# Bluetooth.net
KiCad netlist of a schematic drawn in Altium Designer
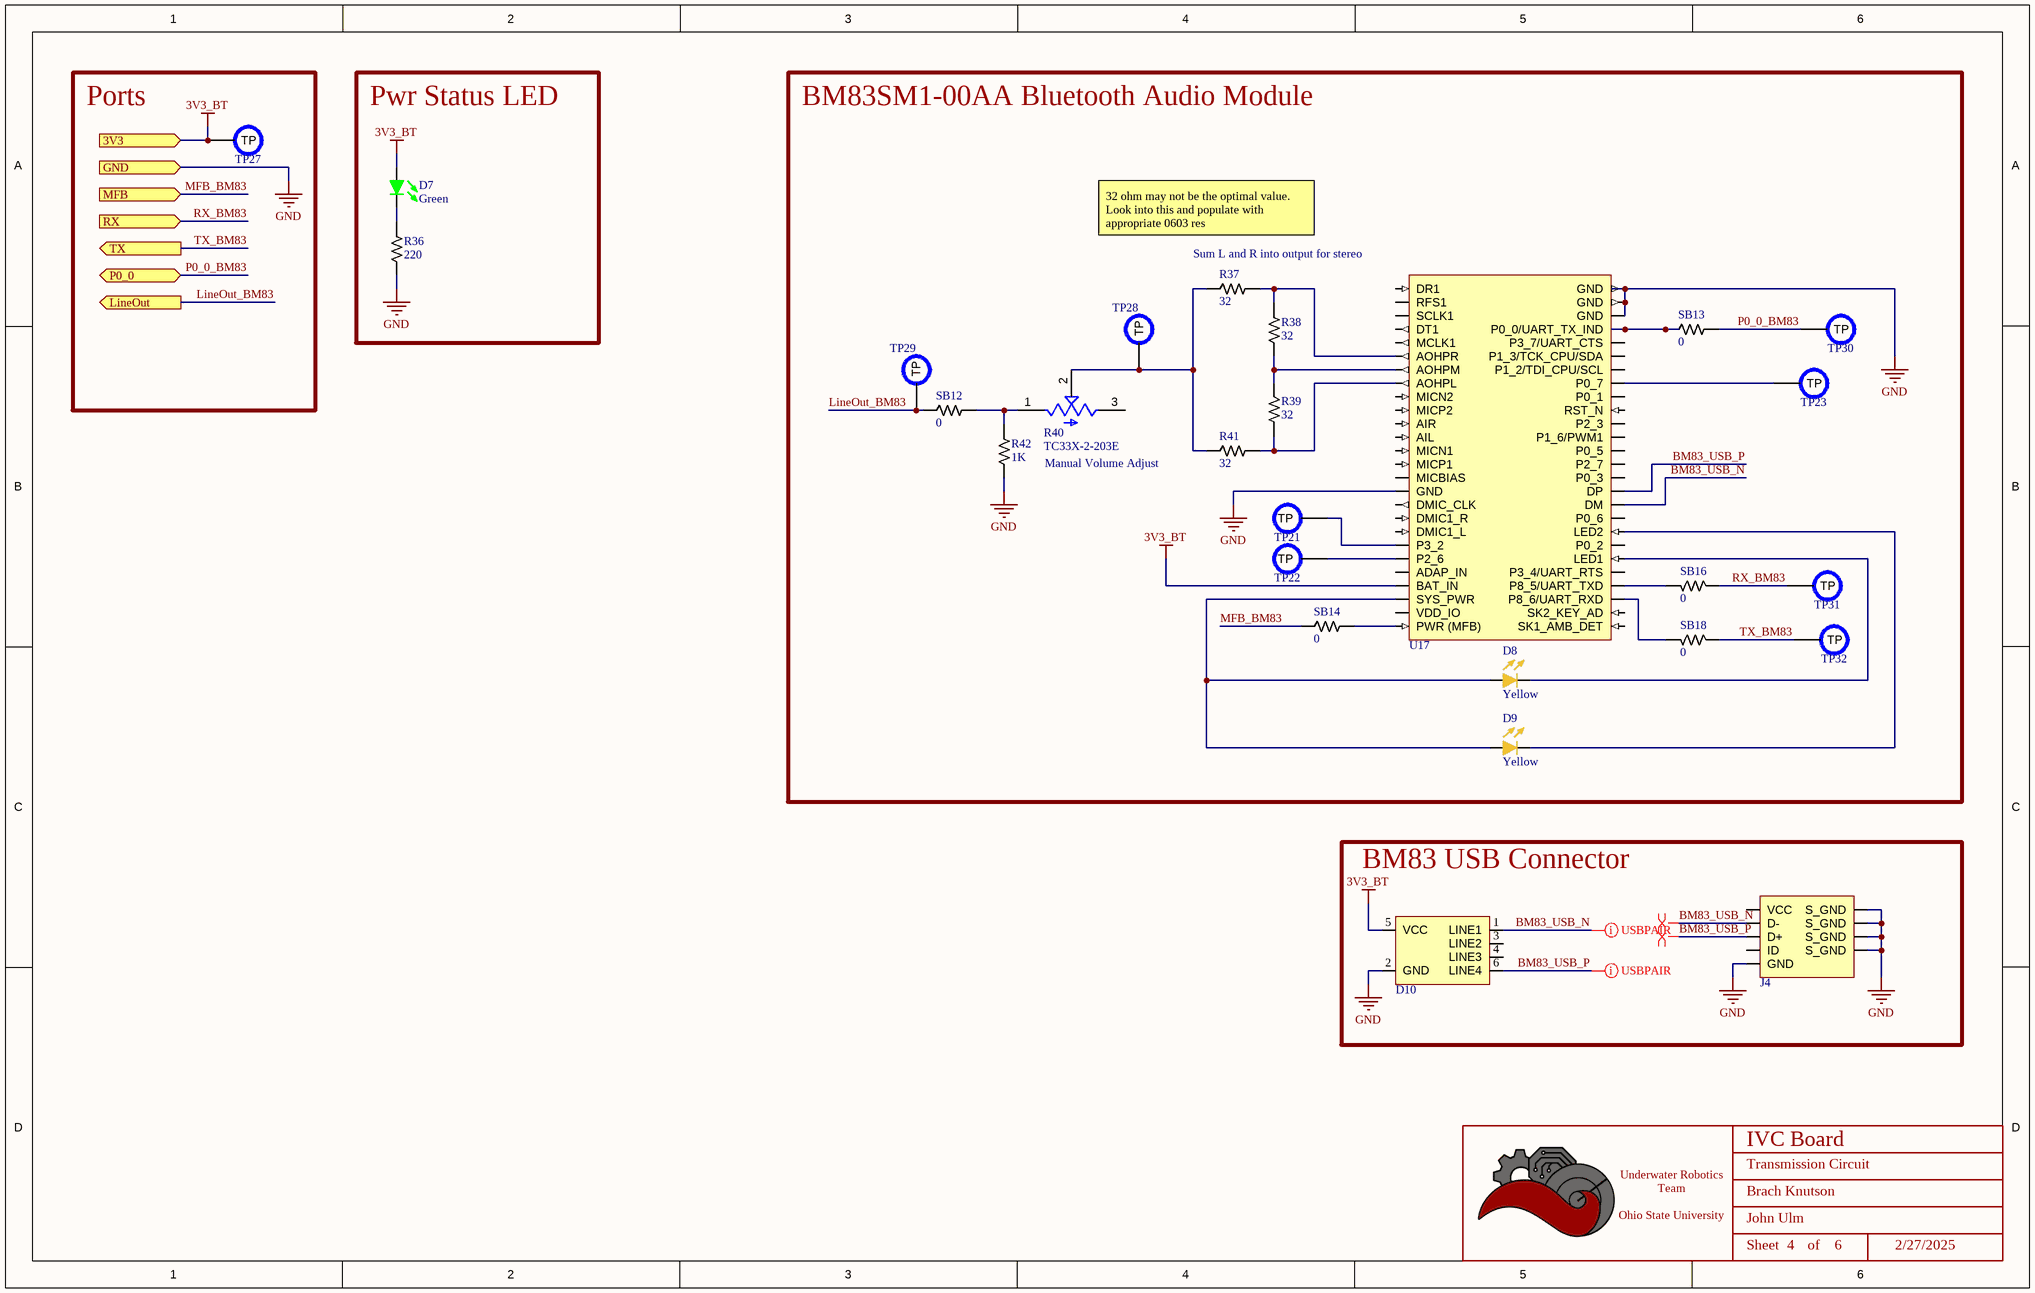
[diagram p0: Bluetooth.SchDoc]

(export (version "E")
  (design (tool "Eeschema 10.0.6"))
  (components
    (comp (ref "D7")
      (value "150060GS75000")
      (footprint "LED_0603")
      (description "LED Green Vf= 3.2V If = 0.025A\r\n150060GS75000")
      (fields (field (name "COLOR") "Green") (field (name "MADE BY") "Flip B"))
      (libsource (lib "Diodes") (part "LED_Green_0603_3.2V"))
    )
    (comp (ref "D8")
      (value "150060YS75000")
      (footprint "LED_0603")
      (description "LED Yellow Vf= 2V If = 0.020A\r\n150060YS75000")
      (fields (field (name "COLOR") "Yellow") (field (name "MADE BY") "Robert Pafford"))
      (libsource (lib "Diodes") (part "LED_Yellow_0603"))
    )
    (comp (ref "D9")
      (value "150060YS75000")
      (footprint "LED_0603")
      (description "LED Yellow Vf= 2V If = 0.020A\r\n150060YS75000")
      (fields (field (name "COLOR") "Yellow") (field (name "MADE BY") "Robert Pafford"))
      (libsource (lib "Diodes") (part "LED_Yellow_0603"))
    )
    (comp (ref "D10")
      (value "TVS DIODE 5VWM 25VC SOT23-6")
      (footprint "SOT 23-6L")
      (description "25V Clamp 6A (8/20µs) Ipp Tvs Diode Surface Mount SOT-23-6")
      (fields (field (name "MADE BY") "Robert Pafford"))
      (libsource (lib "Diodes") (part "RCLAMP0504S.TCT"))
    )
    (comp (ref "J4")
      (value "USB_MICRO R/A")
      (footprint "CONN_MINIUSB")
      (description "Amphenol Micro USB-B\r\nUSB2.0 5 Pin Right Angle SMD")
      (fields (field (name "MANUFACTURER") "Amphenol") (field (name "CREATED BY") "Flip B"))
      (libsource (lib "Connectors") (part "CONN_MICROUSB"))
    )
    (comp (ref "R36")
      (value "220 Ohm 5% 1/8W")
      (footprint "RESISTOR_0603")
      (description "RES 220 OHM 5% 1/8W 0603")
      (fields
        (field (name "TOLERANCE") "+/- 5%")
        (field (name "VALUE  (OHMS)") "220")
        (field (name "MADE BY") "John S")
      )
      (libsource (lib "Resistors") (part "RESISTOR_200_0603"))
    )
    (comp (ref "R37")
      (value "32")
      (footprint "RESISTOR_0603")
      (fields (field (name "Comment") "RN73R1JTTD32R0D25"))
      (libsource (lib "Resistors") (part "RES 32 OHM 0.5% 1/10W 0603"))
    )
    (comp (ref "R38")
      (value "32")
      (footprint "RESISTOR_0603")
      (fields (field (name "Comment") "RN73R1JTTD32R0D25"))
      (libsource (lib "Resistors") (part "RES 32 OHM 0.5% 1/10W 0603"))
    )
    (comp (ref "R39")
      (value "32")
      (footprint "RESISTOR_0603")
      (fields (field (name "Comment") "RN73R1JTTD32R0D25"))
      (libsource (lib "Resistors") (part "RES 32 OHM 0.5% 1/10W 0603"))
    )
    (comp (ref "R40")
      (value "TC33X-2-203E")
      (footprint "TRIM_TC33X-2-203E")
      (description "20 kOhms 0.1W, 1/10W J Lead Surface Mount Trimmer Potentiometer Cermet 1 Turn Top Adjustment")
      (fields (field (name "MF") "Bourns") (field (name "DIGI-KEY_PART_NUMBER") "TC33X-2-203ECT-ND"))
      (libsource (lib "Resistors") (part "TC33X-2-203E"))
    )
    (comp (ref "R41")
      (value "32")
      (footprint "RESISTOR_0603")
      (fields (field (name "Comment") "RN73R1JTTD32R0D25"))
      (libsource (lib "Resistors") (part "RES 32 OHM 0.5% 1/10W 0603"))
    )
    (comp (ref "R42")
      (value "1k Ohm 5% 1/8W")
      (footprint "RESISTOR_0603")
      (description "RES 1k OHM 5% 1/8W 0603")
      (fields
        (field (name "TOLERANCE") "+/- 5%")
        (field (name "VALUE  (OHMS)") "1K")
        (field (name "MADE BY") "Robert Pafford")
      )
      (libsource (lib "Resistors") (part "RESISTOR_1K_0603"))
    )
    (comp (ref "SB12")
      (value "0 Ohm Jumper No Fit")
      (footprint "RESISTOR_0603")
      (description "0 Ohm Jumper No Fit for Solder Bridge")
      (fields (field (name "VALUE  (OHMS)") "0") (field (name "MADE BY") "Robert Pafford"))
      (libsource (lib "Resistors") (part "JUMPER_0_0603"))
    )
    (comp (ref "SB13")
      (value "0 Ohm Jumper No Fit")
      (footprint "RESISTOR_0603")
      (description "0 Ohm Jumper No Fit for Solder Bridge")
      (fields (field (name "VALUE  (OHMS)") "0") (field (name "MADE BY") "Robert Pafford"))
      (libsource (lib "Resistors") (part "JUMPER_0_0603"))
    )
    (comp (ref "SB14")
      (value "0 Ohm Jumper No Fit")
      (footprint "RESISTOR_0603")
      (description "0 Ohm Jumper No Fit for Solder Bridge")
      (fields (field (name "VALUE  (OHMS)") "0") (field (name "MADE BY") "Robert Pafford"))
      (libsource (lib "Resistors") (part "JUMPER_0_0603"))
    )
    (comp (ref "SB16")
      (value "0 Ohm Jumper No Fit")
      (footprint "RESISTOR_0603")
      (description "0 Ohm Jumper No Fit for Solder Bridge")
      (fields (field (name "VALUE  (OHMS)") "0") (field (name "MADE BY") "Robert Pafford"))
      (libsource (lib "Resistors") (part "JUMPER_0_0603"))
    )
    (comp (ref "SB18")
      (value "0 Ohm Jumper No Fit")
      (footprint "RESISTOR_0603")
      (description "0 Ohm Jumper No Fit for Solder Bridge")
      (fields (field (name "VALUE  (OHMS)") "0") (field (name "MADE BY") "Robert Pafford"))
      (libsource (lib "Resistors") (part "JUMPER_0_0603"))
    )
    (comp (ref "TP21")
      (value "PCB Test Point")
      (footprint "TESTPOINT_1.2MM")
      (fields (field (name "MADE BY") "Robert Pafford"))
      (libsource (lib "Connectors") (part "TESTPOINT"))
    )
    (comp (ref "TP22")
      (value "PCB Test Point")
      (footprint "TESTPOINT_1.2MM")
      (fields (field (name "MADE BY") "Robert Pafford"))
      (libsource (lib "Connectors") (part "TESTPOINT"))
    )
    (comp (ref "TP23")
      (value "PCB Test Point")
      (footprint "TESTPOINT_1.2MM")
      (fields (field (name "MADE BY") "Robert Pafford"))
      (libsource (lib "Connectors") (part "TESTPOINT"))
    )
    (comp (ref "TP27")
      (value "PCB Test Point")
      (footprint "TESTPOINT_1.2MM")
      (fields (field (name "MADE BY") "Robert Pafford"))
      (libsource (lib "Connectors") (part "TESTPOINT"))
    )
    (comp (ref "TP28")
      (value "PCB Test Point")
      (footprint "TESTPOINT_1.2MM")
      (fields (field (name "MADE BY") "Robert Pafford"))
      (libsource (lib "Connectors") (part "TESTPOINT"))
    )
    (comp (ref "TP29")
      (value "PCB Test Point")
      (footprint "TESTPOINT_1.2MM")
      (fields (field (name "MADE BY") "Robert Pafford"))
      (libsource (lib "Connectors") (part "TESTPOINT"))
    )
    (comp (ref "TP30")
      (value "PCB Test Point")
      (footprint "TESTPOINT_1.2MM")
      (fields (field (name "MADE BY") "Robert Pafford"))
      (libsource (lib "Connectors") (part "TESTPOINT"))
    )
    (comp (ref "TP31")
      (value "PCB Test Point")
      (footprint "TESTPOINT_1.2MM")
      (fields (field (name "MADE BY") "Robert Pafford"))
      (libsource (lib "Connectors") (part "TESTPOINT"))
    )
    (comp (ref "TP32")
      (value "PCB Test Point")
      (footprint "TESTPOINT_1.2MM")
      (fields (field (name "MADE BY") "Robert Pafford"))
      (libsource (lib "Connectors") (part "TESTPOINT"))
    )
    (comp (ref "U17")
      (value "RF TXRX MOD BT PCB TH SMD")
      (footprint "BM83SM1-00AA")
      (description "Bluetooth Bluetooth v5.0 Transceiver Module 2.4GHz ~ 2.48GHz PCB Trace Surface Mount")
      (libsource (lib "Modules") (part "BM83SM1-00AA"))
    )
  )
  (nets
    (net (code "1") (name "/BM83_USB_N") (class "Default")
      (node (ref "D10") (pin "1") (pinfunction "LINE1_1") (pintype "passive"))
      (node (ref "J4") (pin "2") (pinfunction "D-_2") (pintype "passive"))
      (node (ref "U17") (pin "36") (pinfunction "DM_36") (pintype "bidirectional"))
    )
    (net (code "2") (name "/BM83_USB_P") (class "Default")
      (node (ref "D10") (pin "6") (pinfunction "LINE4_6") (pintype "passive"))
      (node (ref "J4") (pin "3") (pinfunction "D+_3") (pintype "passive"))
      (node (ref "U17") (pin "37") (pinfunction "DP_37") (pintype "bidirectional"))
    )
    (net (code "3") (name "/LineOut_BM83") (class "Default")
      (node (ref "SB12") (pin "2") (pinfunction "2_2") (pintype "passive"))
      (node (ref "TP29") (pin "TP") (pinfunction "TP_TP") (pintype "passive"))
    )
    (net (code "4") (name "/MFB_BM83") (class "Default")
      (node (ref "SB14") (pin "2") (pinfunction "2_2") (pintype "passive"))
    )
    (net (code "5") (name "/P0_0_BM83") (class "Default")
      (node (ref "SB13") (pin "1") (pinfunction "1_1") (pintype "passive"))
      (node (ref "TP30") (pin "TP") (pinfunction "TP_TP") (pintype "passive"))
    )
    (net (code "6") (name "/RX_BM83") (class "Default")
      (node (ref "SB16") (pin "2") (pinfunction "2_2") (pintype "passive"))
      (node (ref "TP31") (pin "TP") (pinfunction "TP_TP") (pintype "passive"))
    )
    (net (code "7") (name "/TX_BM83") (class "Default")
      (node (ref "SB18") (pin "2") (pinfunction "2_2") (pintype "passive"))
      (node (ref "TP32") (pin "TP") (pinfunction "TP_TP") (pintype "passive"))
    )
    (net (code "8") (name "3V3_BT") (class "Default")
      (node (ref "D10") (pin "5") (pinfunction "VCC_5") (pintype "power_in"))
      (node (ref "D7") (pin "1") (pinfunction "1_1") (pintype "passive"))
      (node (ref "TP27") (pin "TP") (pinfunction "TP_TP") (pintype "passive"))
      (node (ref "U17") (pin "23") (pinfunction "BAT_IN_23") (pintype "power_in"))
    )
    (net (code "9") (name "GND") (class "Default")
      (node (ref "D10") (pin "2") (pinfunction "GND_2") (pintype "power_in"))
      (node (ref "J4") (pin "5") (pinfunction "GND_5") (pintype "passive"))
      (node (ref "J4") (pin "6") (pinfunction "S_GND_6") (pintype "passive"))
      (node (ref "J4") (pin "7") (pinfunction "S_GND_7") (pintype "passive"))
      (node (ref "J4") (pin "8") (pinfunction "S_GND_8") (pintype "passive"))
      (node (ref "J4") (pin "9") (pinfunction "S_GND_9") (pintype "passive"))
      (node (ref "R36") (pin "2") (pinfunction "2_2") (pintype "passive"))
      (node (ref "R42") (pin "2") (pinfunction "2_2") (pintype "passive"))
      (node (ref "U17") (pin "16") (pinfunction "GND_16") (pintype "power_in"))
      (node (ref "U17") (pin "50") (pinfunction "GND_50") (pintype "power_in"))
      (node (ref "U17") (pin "51") (pinfunction "GND_51") (pintype "output"))
      (node (ref "U17") (pin "52") (pinfunction "GND_52") (pintype "output"))
    )
    (net (code "10") (name "Net-(D7-Pad2)") (class "Default")
      (node (ref "D7") (pin "2") (pinfunction "2_2") (pintype "passive"))
      (node (ref "R36") (pin "1") (pinfunction "1_1") (pintype "passive"))
    )
    (net (code "11") (name "Net-(R40-CCW)") (class "Default")
      (node (ref "R40") (pin "1") (pinfunction "CCW_1") (pintype "passive"))
      (node (ref "R42") (pin "1") (pinfunction "1_1") (pintype "passive"))
      (node (ref "SB12") (pin "1") (pinfunction "1_1") (pintype "passive"))
    )
    (net (code "12") (name "Net-(R40-W)") (class "Default")
      (node (ref "R37") (pin "2") (pinfunction "2_2") (pintype "passive"))
      (node (ref "R40") (pin "2") (pinfunction "W_2") (pintype "passive"))
      (node (ref "R41") (pin "2") (pinfunction "2_2") (pintype "passive"))
      (node (ref "TP28") (pin "TP") (pinfunction "TP_TP") (pintype "passive"))
    )
    (net (code "13") (name "Net-(U17-AOHPL)") (class "Default")
      (node (ref "R39") (pin "1") (pinfunction "1_1") (pintype "passive"))
      (node (ref "R41") (pin "1") (pinfunction "1_1") (pintype "passive"))
      (node (ref "U17") (pin "8") (pinfunction "AOHPL_8") (pintype "output"))
    )
    (net (code "14") (name "Net-(U17-AOHPM)") (class "Default")
      (node (ref "R38") (pin "2") (pinfunction "2_2") (pintype "passive"))
      (node (ref "R39") (pin "2") (pinfunction "2_2") (pintype "passive"))
      (node (ref "U17") (pin "7") (pinfunction "AOHPM_7") (pintype "output"))
    )
    (net (code "15") (name "Net-(U17-AOHPR)") (class "Default")
      (node (ref "R37") (pin "1") (pinfunction "1_1") (pintype "passive"))
      (node (ref "R38") (pin "1") (pinfunction "1_1") (pintype "passive"))
      (node (ref "U17") (pin "6") (pinfunction "AOHPR_6") (pintype "output"))
    )
    (net (code "16") (name "Net-(U17-LED1)") (class "Default")
      (node (ref "D8") (pin "2") (pinfunction "2_2") (pintype "passive"))
      (node (ref "U17") (pin "32") (pinfunction "LED1_32") (pintype "input"))
    )
    (net (code "17") (name "Net-(U17-LED2)") (class "Default")
      (node (ref "D9") (pin "2") (pinfunction "2_2") (pintype "passive"))
      (node (ref "U17") (pin "34") (pinfunction "LED2_34") (pintype "input"))
    )
    (net (code "18") (name "Net-(U17-P0_0{slash}UART_TX_IND)") (class "Default")
      (node (ref "SB13") (pin "2") (pinfunction "2_2") (pintype "passive"))
      (node (ref "U17") (pin "49") (pinfunction "P0_0/UART_TX_IND_49") (pintype "bidirectional"))
    )
    (net (code "19") (name "Net-(U17-P0_7)") (class "Default")
      (node (ref "TP23") (pin "TP") (pinfunction "TP_TP") (pintype "passive"))
      (node (ref "U17") (pin "45") (pinfunction "P0_7_45") (pintype "bidirectional"))
    )
    (net (code "20") (name "Net-(U17-P2_6)") (class "Default")
      (node (ref "TP22") (pin "TP") (pinfunction "TP_TP") (pintype "passive"))
      (node (ref "U17") (pin "21") (pinfunction "P2_6_21") (pintype "bidirectional"))
    )
    (net (code "21") (name "Net-(U17-P3_2)") (class "Default")
      (node (ref "TP21") (pin "TP") (pinfunction "TP_TP") (pintype "passive"))
      (node (ref "U17") (pin "20") (pinfunction "P3_2_20") (pintype "bidirectional"))
    )
    (net (code "22") (name "Net-(U17-P8_5{slash}UART_TXD)") (class "Default")
      (node (ref "SB16") (pin "1") (pinfunction "1_1") (pintype "passive"))
      (node (ref "U17") (pin "30") (pinfunction "P8_5/UART_TXD_30") (pintype "bidirectional"))
    )
    (net (code "23") (name "Net-(U17-P8_6{slash}UART_RXD)") (class "Default")
      (node (ref "SB18") (pin "1") (pinfunction "1_1") (pintype "passive"))
      (node (ref "U17") (pin "29") (pinfunction "P8_6/UART_RXD_29") (pintype "bidirectional"))
    )
    (net (code "24") (name "Net-(U17-PWR_(MFB))") (class "Default")
      (node (ref "SB14") (pin "1") (pinfunction "1_1") (pintype "passive"))
      (node (ref "U17") (pin "26") (pinfunction "PWR_(MFB)_26") (pintype "input"))
    )
    (net (code "25") (name "Net-(U17-SYS_PWR)") (class "Default")
      (node (ref "D8") (pin "1") (pinfunction "1_1") (pintype "passive"))
      (node (ref "D9") (pin "1") (pinfunction "1_1") (pintype "passive"))
      (node (ref "U17") (pin "24") (pinfunction "SYS_PWR_24") (pintype "power_in"))
    )
    (net (code "26") (name "unconnected-(D10-LINE2-Pad3)") (class "Default")
      (node (ref "D10") (pin "3") (pinfunction "LINE2_3") (pintype "passive"))
    )
    (net (code "27") (name "unconnected-(D10-LINE3-Pad4)") (class "Default")
      (node (ref "D10") (pin "4") (pinfunction "LINE3_4") (pintype "passive"))
    )
    (net (code "28") (name "unconnected-(J4-ID-Pad4)") (class "Default")
      (node (ref "J4") (pin "4") (pinfunction "ID_4") (pintype "passive"))
    )
    (net (code "29") (name "unconnected-(J4-VCC-Pad1)") (class "Default")
      (node (ref "J4") (pin "1") (pinfunction "VCC_1") (pintype "passive"))
    )
    (net (code "30") (name "unconnected-(R40-CW-Pad3)") (class "Default")
      (node (ref "R40") (pin "3") (pinfunction "CW_3") (pintype "passive"))
    )
    (net (code "31") (name "unconnected-(U17-ADAP_IN-Pad22)") (class "Default")
      (node (ref "U17") (pin "22") (pinfunction "ADAP_IN_22") (pintype "power_in"))
    )
    (net (code "32") (name "unconnected-(U17-AIL-Pad12)") (class "Default")
      (node (ref "U17") (pin "12") (pinfunction "AIL_12") (pintype "input"))
    )
    (net (code "33") (name "unconnected-(U17-AIR-Pad11)") (class "Default")
      (node (ref "U17") (pin "11") (pinfunction "AIR_11") (pintype "input"))
    )
    (net (code "34") (name "unconnected-(U17-DMIC1_L-Pad19)") (class "Default")
      (node (ref "U17") (pin "19") (pinfunction "DMIC1_L_19") (pintype "input"))
    )
    (net (code "35") (name "unconnected-(U17-DMIC1_R-Pad18)") (class "Default")
      (node (ref "U17") (pin "18") (pinfunction "DMIC1_R_18") (pintype "input"))
    )
    (net (code "36") (name "unconnected-(U17-DMIC_CLK-Pad17)") (class "Default")
      (node (ref "U17") (pin "17") (pinfunction "DMIC_CLK_17") (pintype "output"))
    )
    (net (code "37") (name "unconnected-(U17-DR1-Pad1)") (class "Default")
      (node (ref "U17") (pin "1") (pinfunction "DR1_1") (pintype "input"))
    )
    (net (code "38") (name "unconnected-(U17-DT1-Pad4)") (class "Default")
      (node (ref "U17") (pin "4") (pinfunction "DT1_4") (pintype "output"))
    )
    (net (code "39") (name "unconnected-(U17-MCLK1-Pad5)") (class "Default")
      (node (ref "U17") (pin "5") (pinfunction "MCLK1_5") (pintype "output"))
    )
    (net (code "40") (name "unconnected-(U17-MICBIAS-Pad15)") (class "Default")
      (node (ref "U17") (pin "15") (pinfunction "MICBIAS_15") (pintype "power_in"))
    )
    (net (code "41") (name "unconnected-(U17-MICN1-Pad13)") (class "Default")
      (node (ref "U17") (pin "13") (pinfunction "MICN1_13") (pintype "input"))
    )
    (net (code "42") (name "unconnected-(U17-MICN2-Pad9)") (class "Default")
      (node (ref "U17") (pin "9") (pinfunction "MICN2_9") (pintype "input"))
    )
    (net (code "43") (name "unconnected-(U17-MICP1-Pad14)") (class "Default")
      (node (ref "U17") (pin "14") (pinfunction "MICP1_14") (pintype "input"))
    )
    (net (code "44") (name "unconnected-(U17-MICP2-Pad10)") (class "Default")
      (node (ref "U17") (pin "10") (pinfunction "MICP2_10") (pintype "input"))
    )
    (net (code "45") (name "unconnected-(U17-P0_1-Pad44)") (class "Default")
      (node (ref "U17") (pin "44") (pinfunction "P0_1_44") (pintype "bidirectional"))
    )
    (net (code "46") (name "unconnected-(U17-P0_2-Pad33)") (class "Default")
      (node (ref "U17") (pin "33") (pinfunction "P0_2_33") (pintype "bidirectional"))
    )
    (net (code "47") (name "unconnected-(U17-P0_3-Pad38)") (class "Default")
      (node (ref "U17") (pin "38") (pinfunction "P0_3_38") (pintype "bidirectional"))
    )
    (net (code "48") (name "unconnected-(U17-P0_5-Pad40)") (class "Default")
      (node (ref "U17") (pin "40") (pinfunction "P0_5_40") (pintype "bidirectional"))
    )
    (net (code "49") (name "unconnected-(U17-P0_6-Pad35)") (class "Default")
      (node (ref "U17") (pin "35") (pinfunction "P0_6_35") (pintype "bidirectional"))
    )
    (net (code "50") (name "unconnected-(U17-P1_2{slash}TDI_CPU{slash}SCL-Pad46)") (class "Default")
      (node (ref "U17") (pin "46") (pinfunction "P1_2/TDI_CPU/SCL_46") (pintype "bidirectional"))
    )
    (net (code "51") (name "unconnected-(U17-P1_3{slash}TCK_CPU{slash}SDA-Pad47)") (class "Default")
      (node (ref "U17") (pin "47") (pinfunction "P1_3/TCK_CPU/SDA_47") (pintype "bidirectional"))
    )
    (net (code "52") (name "unconnected-(U17-P1_6{slash}PWM1-Pad41)") (class "Default")
      (node (ref "U17") (pin "41") (pinfunction "P1_6/PWM1_41") (pintype "bidirectional"))
    )
    (net (code "53") (name "unconnected-(U17-P2_3-Pad42)") (class "Default")
      (node (ref "U17") (pin "42") (pinfunction "P2_3_42") (pintype "bidirectional"))
    )
    (net (code "54") (name "unconnected-(U17-P2_7-Pad39)") (class "Default")
      (node (ref "U17") (pin "39") (pinfunction "P2_7_39") (pintype "bidirectional"))
    )
    (net (code "55") (name "unconnected-(U17-P3_4{slash}UART_RTS-Pad31)") (class "Default")
      (node (ref "U17") (pin "31") (pinfunction "P3_4/UART_RTS_31") (pintype "bidirectional"))
    )
    (net (code "56") (name "unconnected-(U17-P3_7{slash}UART_CTS-Pad48)") (class "Default")
      (node (ref "U17") (pin "48") (pinfunction "P3_7/UART_CTS_48") (pintype "bidirectional"))
    )
    (net (code "57") (name "unconnected-(U17-RFS1-Pad2)") (class "Default")
      (node (ref "U17") (pin "2") (pinfunction "RFS1_2") (pintype "bidirectional"))
    )
    (net (code "58") (name "unconnected-(U17-RST_N-Pad43)") (class "Default")
      (node (ref "U17") (pin "43") (pinfunction "RST_N_43") (pintype "input"))
    )
    (net (code "59") (name "unconnected-(U17-SCLK1-Pad3)") (class "Default")
      (node (ref "U17") (pin "3") (pinfunction "SCLK1_3") (pintype "bidirectional"))
    )
    (net (code "60") (name "unconnected-(U17-SK1_AMB_DET-Pad27)") (class "Default")
      (node (ref "U17") (pin "27") (pinfunction "SK1_AMB_DET_27") (pintype "input"))
    )
    (net (code "61") (name "unconnected-(U17-SK2_KEY_AD-Pad28)") (class "Default")
      (node (ref "U17") (pin "28") (pinfunction "SK2_KEY_AD_28") (pintype "input"))
    )
    (net (code "62") (name "unconnected-(U17-VDD_IO-Pad25)") (class "Default")
      (node (ref "U17") (pin "25") (pinfunction "VDD_IO_25") (pintype "power_in"))
    )
  )
)
